# SNAC_7ch_SMS_3D_Dongle.net
KiCad netlist of a schematic drawn in EAGLE
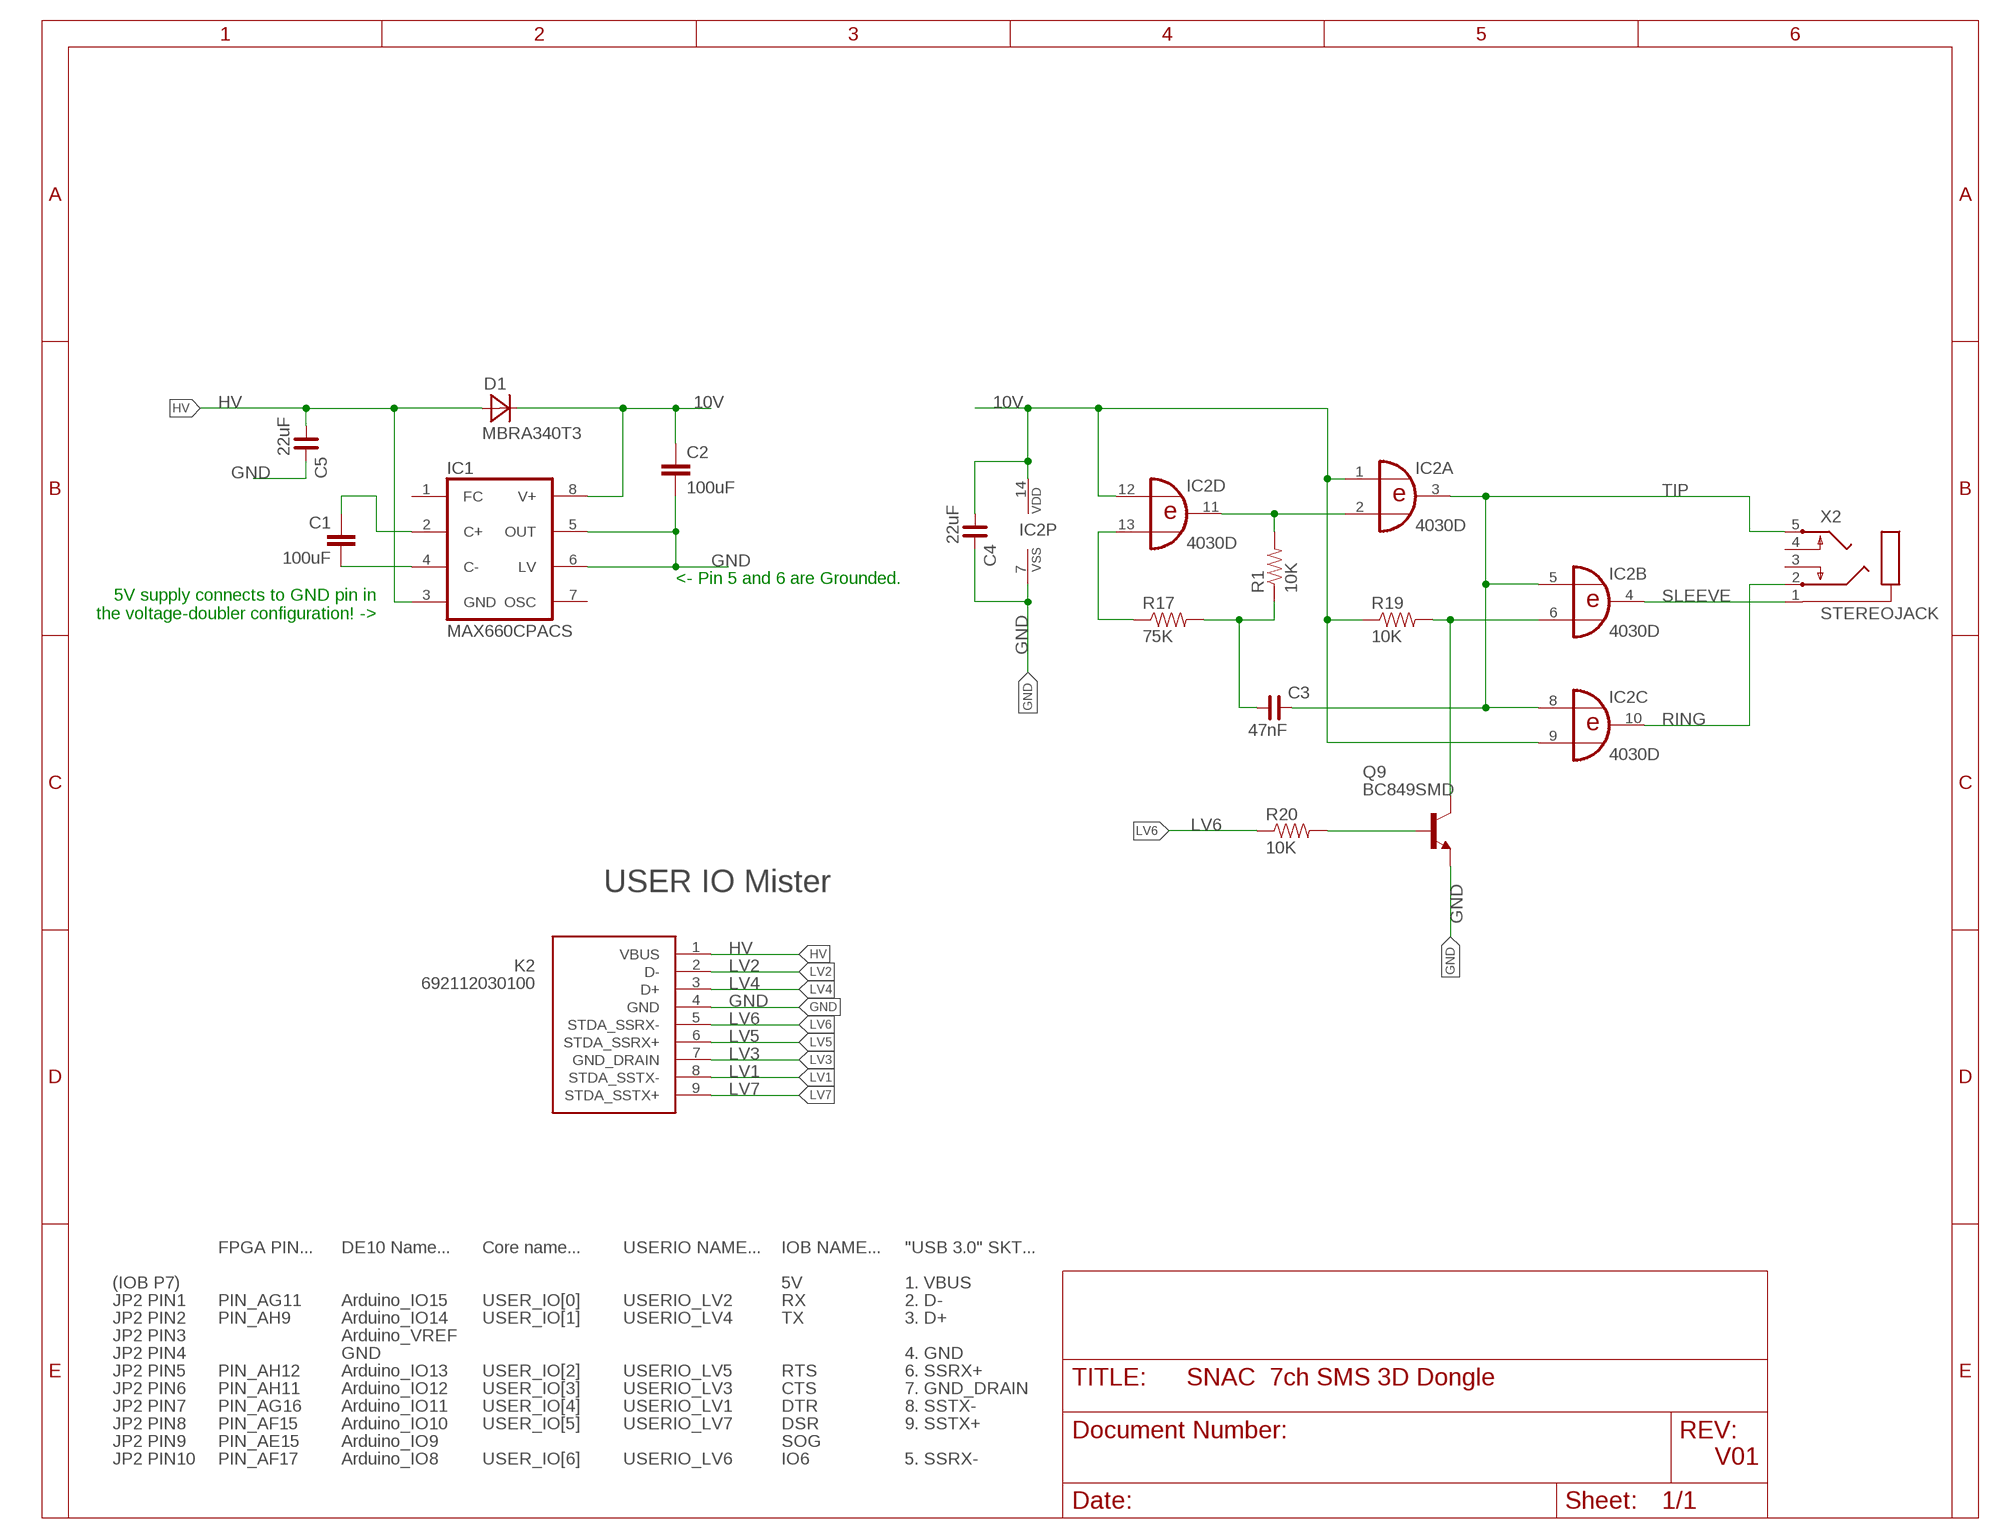
[diagram p0: schematic, sheet 1]

(export (version "E")
  (design (tool "Eeschema 10.0.6"))
  (components
    (comp (ref "C1")
      (value "100uF")
      (footprint "eagle-import:C1210")
      (libsource (lib "eagle-import") (part "C-EUC1210"))
    )
    (comp (ref "C2")
      (value "100uF")
      (footprint "eagle-import:C1210")
      (libsource (lib "eagle-import") (part "C-EUC1210"))
    )
    (comp (ref "C3")
      (value "47nF")
      (footprint "eagle-import:C0805")
      (libsource (lib "eagle-import") (part "C_0805"))
    )
    (comp (ref "C4")
      (value "22uF")
      (footprint "eagle-import:C0805")
      (libsource (lib "eagle-import") (part "C_0805"))
    )
    (comp (ref "C5")
      (value "22uF")
      (footprint "eagle-import:C0805")
      (libsource (lib "eagle-import") (part "C_0805"))
    )
    (comp (ref "D1")
      (value "MBRA340T3")
      (footprint "eagle-import:SMA")
      (libsource (lib "eagle-import") (part "MBRA340T3"))
    )
    (comp (ref "IC1")
      (value "MAX660CPACS")
      (footprint "eagle-import:SO08")
      (libsource (lib "eagle-import") (part "MAX660CPACS"))
    )
    (comp (ref "IC2")
      (value "4030D")
      (footprint "eagle-import:SO14")
      (libsource (lib "eagle-import") (part "4030D"))
    )
    (comp (ref "K2")
      (value "692112030100")
      (footprint "eagle-import:692112030100")
      (libsource (lib "eagle-import") (part "692112030100"))
    )
    (comp (ref "Q9")
      (value "BC849SMD")
      (footprint "eagle-import:SOT23-BEC")
      (libsource (lib "eagle-import") (part "BC849SMD"))
    )
    (comp (ref "R1")
      (value "10K")
      (footprint "eagle-import:0603-RES")
      (libsource (lib "eagle-import") (part "RESISTOR0603-RES"))
    )
    (comp (ref "R17")
      (value "75K")
      (footprint "eagle-import:0603-RES")
      (libsource (lib "eagle-import") (part "RESISTOR0603-RES"))
    )
    (comp (ref "R19")
      (value "10K")
      (footprint "eagle-import:0603-RES")
      (libsource (lib "eagle-import") (part "RESISTOR0603-RES"))
    )
    (comp (ref "R20")
      (value "10K")
      (footprint "eagle-import:0603-RES")
      (libsource (lib "eagle-import") (part "RESISTOR0603-RES"))
    )
    (comp (ref "X2")
      (value "STEREOJACK")
      (footprint "eagle-import:STX3100")
      (libsource (lib "eagle-import") (part "STEREOJACK"))
    )
  )
  (nets
    (net (code "1") (name "/10V") (class "Default")
      (node (ref "C2") (pin "1") (pinfunction "1_1") (pintype "passive"))
      (node (ref "C4") (pin "1") (pinfunction "1_1") (pintype "passive"))
      (node (ref "D1") (pin "C") (pinfunction "C_C") (pintype "passive"))
      (node (ref "IC1") (pin "8") (pinfunction "V+_8") (pintype "power_in"))
      (node (ref "IC2") (pin "1") (pinfunction "I0_1") (pintype "input"))
      (node (ref "IC2") (pin "12") (pinfunction "I0_12") (pintype "input"))
      (node (ref "IC2") (pin "14") (pinfunction "VDD_14") (pintype "power_in"))
      (node (ref "IC2") (pin "9") (pinfunction "I1_9") (pintype "input"))
      (node (ref "R19") (pin "1") (pinfunction "1_1") (pintype "passive"))
    )
    (net (code "2") (name "/RING") (class "Default")
      (node (ref "IC2") (pin "10") (pinfunction "O_10") (pintype "output"))
      (node (ref "X2") (pin "2") (pinfunction "2_2") (pintype "passive"))
    )
    (net (code "3") (name "/SLEEVE") (class "Default")
      (node (ref "IC2") (pin "4") (pinfunction "O_4") (pintype "output"))
      (node (ref "X2") (pin "1") (pinfunction "1_1") (pintype "passive"))
    )
    (net (code "4") (name "/TIP") (class "Default")
      (node (ref "C3") (pin "2") (pinfunction "2_2") (pintype "passive"))
      (node (ref "IC2") (pin "3") (pinfunction "O_3") (pintype "output"))
      (node (ref "IC2") (pin "5") (pinfunction "I0_5") (pintype "input"))
      (node (ref "IC2") (pin "8") (pinfunction "I0_8") (pintype "input"))
      (node (ref "X2") (pin "5") (pinfunction "5_5") (pintype "passive"))
    )
    (net (code "5") (name "GND") (class "Default")
      (node (ref "C2") (pin "2") (pinfunction "2_2") (pintype "passive"))
      (node (ref "C4") (pin "2") (pinfunction "2_2") (pintype "passive"))
      (node (ref "C5") (pin "2") (pinfunction "2_2") (pintype "passive"))
      (node (ref "IC1") (pin "5") (pinfunction "OUT_5") (pintype "power_in"))
      (node (ref "IC1") (pin "6") (pinfunction "LV_6") (pintype "passive"))
      (node (ref "IC2") (pin "7") (pinfunction "VSS_7") (pintype "power_in"))
      (node (ref "K2") (pin "4") (pinfunction "GND_4") (pintype "bidirectional"))
      (node (ref "Q9") (pin "E") (pinfunction "E_E") (pintype "passive"))
    )
    (net (code "6") (name "HV") (class "Default")
      (node (ref "C5") (pin "1") (pinfunction "1_1") (pintype "passive"))
      (node (ref "D1") (pin "A") (pinfunction "A_A") (pintype "passive"))
      (node (ref "IC1") (pin "3") (pinfunction "GND_3") (pintype "power_in"))
      (node (ref "K2") (pin "1") (pinfunction "VBUS_1") (pintype "bidirectional"))
    )
    (net (code "7") (name "LV1") (class "Default")
      (node (ref "K2") (pin "8") (pinfunction "STDA_SSTX-_8") (pintype "bidirectional"))
    )
    (net (code "8") (name "LV2") (class "Default")
      (node (ref "K2") (pin "2") (pinfunction "D-_2") (pintype "bidirectional"))
    )
    (net (code "9") (name "LV3") (class "Default")
      (node (ref "K2") (pin "7") (pinfunction "GND_DRAIN_7") (pintype "bidirectional"))
    )
    (net (code "10") (name "LV4") (class "Default")
      (node (ref "K2") (pin "3") (pinfunction "D+_3") (pintype "bidirectional"))
    )
    (net (code "11") (name "LV5") (class "Default")
      (node (ref "K2") (pin "6") (pinfunction "STDA_SSRX+_6") (pintype "bidirectional"))
    )
    (net (code "12") (name "LV6") (class "Default")
      (node (ref "K2") (pin "5") (pinfunction "STDA_SSRX-_5") (pintype "bidirectional"))
      (node (ref "R20") (pin "1") (pinfunction "1_1") (pintype "passive"))
    )
    (net (code "13") (name "LV7") (class "Default")
      (node (ref "K2") (pin "9") (pinfunction "STDA_SSTX+_9") (pintype "bidirectional"))
    )
    (net (code "14") (name "Net-(C3-Pad1)") (class "Default")
      (node (ref "C3") (pin "1") (pinfunction "1_1") (pintype "passive"))
      (node (ref "R1") (pin "1") (pinfunction "1_1") (pintype "passive"))
      (node (ref "R17") (pin "2") (pinfunction "2_2") (pintype "passive"))
    )
    (net (code "15") (name "Net-(IC1-C+)") (class "Default")
      (node (ref "C1") (pin "1") (pinfunction "1_1") (pintype "passive"))
      (node (ref "IC1") (pin "2") (pinfunction "C+_2") (pintype "passive"))
    )
    (net (code "16") (name "Net-(IC1-C-)") (class "Default")
      (node (ref "C1") (pin "2") (pinfunction "2_2") (pintype "passive"))
      (node (ref "IC1") (pin "4") (pinfunction "C-_4") (pintype "passive"))
    )
    (net (code "17") (name "Net-(IC2A-I1)") (class "Default")
      (node (ref "IC2") (pin "11") (pinfunction "O_11") (pintype "output"))
      (node (ref "IC2") (pin "2") (pinfunction "I1_2") (pintype "input"))
      (node (ref "R1") (pin "2") (pinfunction "2_2") (pintype "passive"))
    )
    (net (code "18") (name "Net-(IC2B-I1)") (class "Default")
      (node (ref "IC2") (pin "6") (pinfunction "I1_6") (pintype "input"))
      (node (ref "Q9") (pin "C") (pinfunction "C_C") (pintype "passive"))
      (node (ref "R19") (pin "2") (pinfunction "2_2") (pintype "passive"))
    )
    (net (code "19") (name "Net-(IC2D-I1)") (class "Default")
      (node (ref "IC2") (pin "13") (pinfunction "I1_13") (pintype "input"))
      (node (ref "R17") (pin "1") (pinfunction "1_1") (pintype "passive"))
    )
    (net (code "20") (name "Net-(Q9-PadB)") (class "Default")
      (node (ref "Q9") (pin "B") (pinfunction "B_B") (pintype "passive"))
      (node (ref "R20") (pin "2") (pinfunction "2_2") (pintype "passive"))
    )
    (net (code "21") (name "unconnected-(IC1-FC-Pad1)") (class "Default")
      (node (ref "IC1") (pin "1") (pinfunction "FC_1") (pintype "input"))
    )
    (net (code "22") (name "unconnected-(IC1-OSC-Pad7)") (class "Default")
      (node (ref "IC1") (pin "7") (pinfunction "OSC_7") (pintype "output"))
    )
    (net (code "23") (name "unconnected-(X2-Pad3)") (class "Default")
      (node (ref "X2") (pin "3") (pinfunction "3_3") (pintype "passive"))
    )
    (net (code "24") (name "unconnected-(X2-Pad4)") (class "Default")
      (node (ref "X2") (pin "4") (pinfunction "4_4") (pintype "passive"))
    )
  )
)
